# EXT_SLOT.net
KiCad netlist of a schematic drawn in Altium Designer
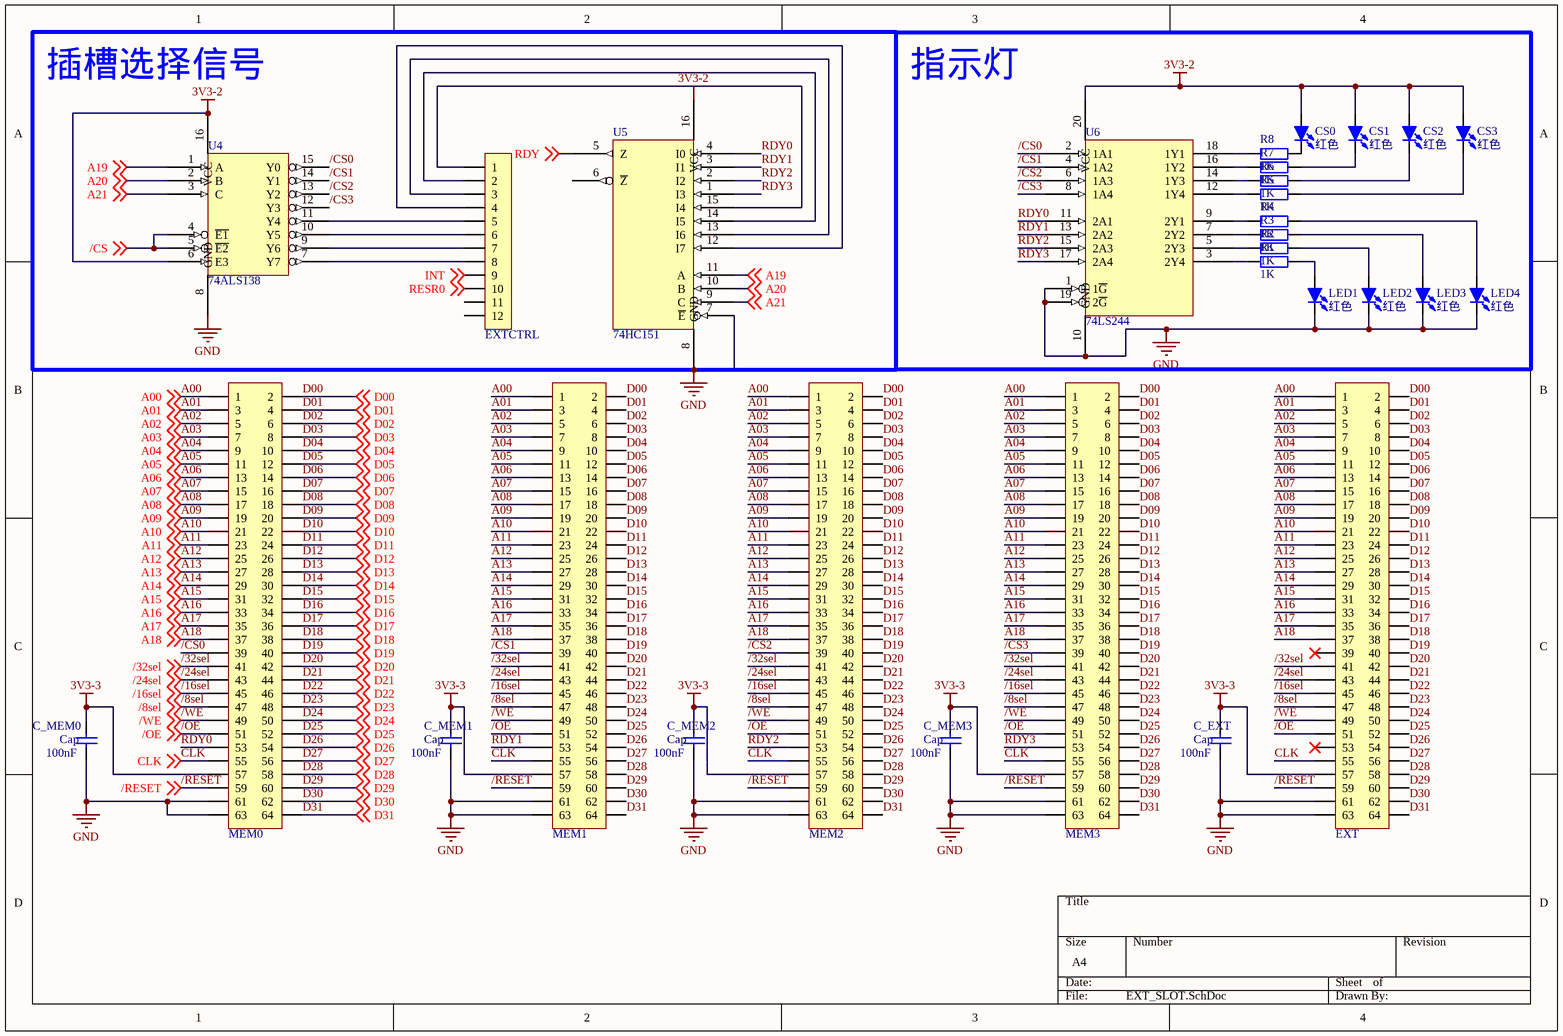
[diagram p0: EXT_SLOT.SchDoc]

(export (version "E")
  (design (tool "Eeschema 10.0.6"))
  (components
    (comp (ref "CS0")
      (value "红色")
      (footprint "LED 5MM-B")
      (description "5mm插件LED")
      (libsource (lib "9.1   - LED") (part "LED-5MM"))
    )
    (comp (ref "CS1")
      (value "红色")
      (footprint "LED 5MM-B")
      (description "5mm插件LED")
      (libsource (lib "9.1   - LED") (part "LED-5MM"))
    )
    (comp (ref "CS2")
      (value "红色")
      (footprint "LED 5MM-B")
      (description "5mm插件LED")
      (libsource (lib "9.1   - LED") (part "LED-5MM"))
    )
    (comp (ref "CS3")
      (value "红色")
      (footprint "LED 5MM-B")
      (description "5mm插件LED")
      (libsource (lib "9.1   - LED") (part "LED-5MM"))
    )
    (comp (ref "C_EXT")
      (value "Cap")
      (footprint "0805")
      (description "Capacitor")
      (fields (field (name "ALTIUM_VALUE") "100nF") (field (name "PUBLISHER") "Altium Limited"))
      (libsource (lib "Miscellaneous Devices") (part "Cap"))
    )
    (comp (ref "C_MEM0")
      (value "Cap")
      (footprint "0805")
      (description "Capacitor")
      (fields (field (name "ALTIUM_VALUE") "100nF") (field (name "PUBLISHER") "Altium Limited"))
      (libsource (lib "Miscellaneous Devices") (part "Cap"))
    )
    (comp (ref "C_MEM1")
      (value "Cap")
      (footprint "0805")
      (description "Capacitor")
      (fields (field (name "ALTIUM_VALUE") "100nF") (field (name "PUBLISHER") "Altium Limited"))
      (libsource (lib "Miscellaneous Devices") (part "Cap"))
    )
    (comp (ref "C_MEM2")
      (value "Cap")
      (footprint "0805")
      (description "Capacitor")
      (fields (field (name "ALTIUM_VALUE") "100nF") (field (name "PUBLISHER") "Altium Limited"))
      (libsource (lib "Miscellaneous Devices") (part "Cap"))
    )
    (comp (ref "C_MEM3")
      (value "Cap")
      (footprint "0805")
      (description "Capacitor")
      (fields (field (name "ALTIUM_VALUE") "100nF") (field (name "PUBLISHER") "Altium Limited"))
      (libsource (lib "Miscellaneous Devices") (part "Cap"))
    )
    (comp (ref "EXT")
      (value "Header 2X32")
      (footprint "IDC2.54-V64D")
      (description "32*2P接插件")
      (libsource (lib "4.5   - 接插件-脚距2.54") (part "Header 32X2"))
    )
    (comp (ref "EXTCTRL")
      (value "HDR-1X12")
      (footprint "SIP12")
      (description "12P接插件")
      (libsource (lib "4.5   - 接插件-脚距2.54") (part "Header 12"))
    )
    (comp (ref "LED1")
      (value "红色")
      (footprint "LED 5MM-B")
      (description "5mm插件LED")
      (libsource (lib "9.1   - LED") (part "LED-5MM"))
    )
    (comp (ref "LED2")
      (value "红色")
      (footprint "LED 5MM-B")
      (description "5mm插件LED")
      (libsource (lib "9.1   - LED") (part "LED-5MM"))
    )
    (comp (ref "LED3")
      (value "红色")
      (footprint "LED 5MM-B")
      (description "5mm插件LED")
      (libsource (lib "9.1   - LED") (part "LED-5MM"))
    )
    (comp (ref "LED4")
      (value "红色")
      (footprint "LED 5MM-B")
      (description "5mm插件LED")
      (libsource (lib "9.1   - LED") (part "LED-5MM"))
    )
    (comp (ref "MEM0")
      (value "Header 2X32")
      (footprint "IDC2.54-V64D")
      (description "32*2P接插件")
      (libsource (lib "4.5   - 接插件-脚距2.54") (part "Header 32X2"))
    )
    (comp (ref "MEM1")
      (value "Header 2X32")
      (footprint "IDC2.54-V64D")
      (description "32*2P接插件")
      (libsource (lib "4.5   - 接插件-脚距2.54") (part "Header 32X2"))
    )
    (comp (ref "MEM2")
      (value "Header 2X32")
      (footprint "IDC2.54-V64D")
      (description "32*2P接插件")
      (libsource (lib "4.5   - 接插件-脚距2.54") (part "Header 32X2"))
    )
    (comp (ref "MEM3")
      (value "Header 2X32")
      (footprint "IDC2.54-V64D")
      (description "32*2P接插件")
      (libsource (lib "4.5   - 接插件-脚距2.54") (part "Header 32X2"))
    )
    (comp (ref "R1")
      (value "1K")
      (footprint "0805")
      (description "贴片电阻")
      (libsource (lib "3.1   - 电阻-电容-电感") (part "R"))
    )
    (comp (ref "R2")
      (value "1K")
      (footprint "0805")
      (description "贴片电阻")
      (libsource (lib "3.1   - 电阻-电容-电感") (part "R"))
    )
    (comp (ref "R3")
      (value "1K")
      (footprint "0805")
      (description "贴片电阻")
      (libsource (lib "3.1   - 电阻-电容-电感") (part "R"))
    )
    (comp (ref "R4")
      (value "1K")
      (footprint "0805")
      (description "贴片电阻")
      (libsource (lib "3.1   - 电阻-电容-电感") (part "R"))
    )
    (comp (ref "R5")
      (value "1K")
      (footprint "0805")
      (description "贴片电阻")
      (libsource (lib "3.1   - 电阻-电容-电感") (part "R"))
    )
    (comp (ref "R6")
      (value "1K")
      (footprint "0805")
      (description "贴片电阻")
      (libsource (lib "3.1   - 电阻-电容-电感") (part "R"))
    )
    (comp (ref "R7")
      (value "1K")
      (footprint "0805")
      (description "贴片电阻")
      (libsource (lib "3.1   - 电阻-电容-电感") (part "R"))
    )
    (comp (ref "R8")
      (value "1K")
      (footprint "0805")
      (description "贴片电阻")
      (libsource (lib "3.1   - 电阻-电容-电感") (part "R"))
    )
    (comp (ref "U4") (value "74ALS138") (footprint "SO-16") (libsource (lib "TTL74系列IC") (part "74ALS138")))
    (comp (ref "U5") (value "74HC151") (footprint "SO-16") (libsource (lib "TTL74系列IC") (part "74HC151")))
    (comp (ref "U6") (value "74LS244") (footprint "SOJ-20") (libsource (lib "TTL74系列IC") (part "74LS244")))
  )
  (nets
    (net (code "2") (name "/RDY0") (class "Default")
      (node (ref "MEM0") (pin "53") (pinfunction "53_53") (pintype "passive"))
      (node (ref "U5") (pin "4") (pinfunction "I0_4") (pintype "input"))
      (node (ref "U6") (pin "11") (pinfunction "2A1_11") (pintype "input"))
    )
    (net (code "3") (name "/RDY1") (class "Default")
      (node (ref "MEM1") (pin "53") (pinfunction "53_53") (pintype "passive"))
      (node (ref "U5") (pin "3") (pinfunction "I1_3") (pintype "input"))
      (node (ref "U6") (pin "13") (pinfunction "2A2_13") (pintype "input"))
    )
    (net (code "4") (name "/RDY2") (class "Default")
      (node (ref "MEM2") (pin "53") (pinfunction "53_53") (pintype "passive"))
      (node (ref "U5") (pin "2") (pinfunction "I2_2") (pintype "input"))
      (node (ref "U6") (pin "15") (pinfunction "2A3_15") (pintype "input"))
    )
    (net (code "5") (name "/RDY3") (class "Default")
      (node (ref "MEM3") (pin "53") (pinfunction "53_53") (pintype "passive"))
      (node (ref "U5") (pin "1") (pinfunction "I3_1") (pintype "input"))
      (node (ref "U6") (pin "17") (pinfunction "2A4_17") (pintype "input"))
    )
    (net (code "6") (name "/{slash}CS0") (class "Default")
      (node (ref "MEM0") (pin "39") (pinfunction "39_39") (pintype "passive"))
      (node (ref "U4") (pin "15") (pinfunction "Y0_15") (pintype "output"))
      (node (ref "U6") (pin "2") (pinfunction "1A1_2") (pintype "input"))
    )
    (net (code "7") (name "/{slash}CS1") (class "Default")
      (node (ref "MEM1") (pin "39") (pinfunction "39_39") (pintype "passive"))
      (node (ref "U4") (pin "14") (pinfunction "Y1_14") (pintype "output"))
      (node (ref "U6") (pin "4") (pinfunction "1A2_4") (pintype "input"))
    )
    (net (code "8") (name "/{slash}CS2") (class "Default")
      (node (ref "MEM2") (pin "39") (pinfunction "39_39") (pintype "passive"))
      (node (ref "U4") (pin "13") (pinfunction "Y2_13") (pintype "output"))
      (node (ref "U6") (pin "6") (pinfunction "1A3_6") (pintype "input"))
    )
    (net (code "9") (name "/{slash}CS3") (class "Default")
      (node (ref "MEM3") (pin "39") (pinfunction "39_39") (pintype "passive"))
      (node (ref "U4") (pin "12") (pinfunction "Y3_12") (pintype "output"))
      (node (ref "U6") (pin "8") (pinfunction "1A4_8") (pintype "input"))
    )
    (net (code "10") (name "3V3-2") (class "Default")
      (node (ref "CS0") (pin "1") (pinfunction "A_1") (pintype "passive"))
      (node (ref "CS1") (pin "1") (pinfunction "A_1") (pintype "passive"))
      (node (ref "CS2") (pin "1") (pinfunction "A_1") (pintype "passive"))
      (node (ref "CS3") (pin "1") (pinfunction "A_1") (pintype "passive"))
      (node (ref "U4") (pin "16") (pinfunction "VCC_16") (pintype "power_in"))
      (node (ref "U4") (pin "6") (pinfunction "E3_6") (pintype "input"))
      (node (ref "U5") (pin "16") (pinfunction "VCC_16") (pintype "power_in"))
      (node (ref "U6") (pin "20") (pinfunction "VCC_20") (pintype "power_in"))
    )
    (net (code "11") (name "3V3-3") (class "Default")
      (node (ref "C_EXT") (pin "2") (pinfunction "2_2") (pintype "passive"))
      (node (ref "C_MEM0") (pin "2") (pinfunction "2_2") (pintype "passive"))
      (node (ref "C_MEM1") (pin "2") (pinfunction "2_2") (pintype "passive"))
      (node (ref "C_MEM2") (pin "2") (pinfunction "2_2") (pintype "passive"))
      (node (ref "C_MEM3") (pin "2") (pinfunction "2_2") (pintype "passive"))
      (node (ref "EXT") (pin "57") (pinfunction "57_57") (pintype "passive"))
      (node (ref "MEM0") (pin "57") (pinfunction "57_57") (pintype "passive"))
      (node (ref "MEM1") (pin "57") (pinfunction "57_57") (pintype "passive"))
      (node (ref "MEM2") (pin "57") (pinfunction "57_57") (pintype "passive"))
      (node (ref "MEM3") (pin "57") (pinfunction "57_57") (pintype "passive"))
    )
    (net (code "12") (name "A00") (class "Default")
      (node (ref "EXT") (pin "1") (pinfunction "1_1") (pintype "passive"))
      (node (ref "MEM0") (pin "1") (pinfunction "1_1") (pintype "passive"))
      (node (ref "MEM1") (pin "1") (pinfunction "1_1") (pintype "passive"))
      (node (ref "MEM2") (pin "1") (pinfunction "1_1") (pintype "passive"))
      (node (ref "MEM3") (pin "1") (pinfunction "1_1") (pintype "passive"))
    )
    (net (code "13") (name "A01") (class "Default")
      (node (ref "EXT") (pin "3") (pinfunction "3_3") (pintype "passive"))
      (node (ref "MEM0") (pin "3") (pinfunction "3_3") (pintype "passive"))
      (node (ref "MEM1") (pin "3") (pinfunction "3_3") (pintype "passive"))
      (node (ref "MEM2") (pin "3") (pinfunction "3_3") (pintype "passive"))
      (node (ref "MEM3") (pin "3") (pinfunction "3_3") (pintype "passive"))
    )
    (net (code "14") (name "A02") (class "Default")
      (node (ref "EXT") (pin "5") (pinfunction "5_5") (pintype "passive"))
      (node (ref "MEM0") (pin "5") (pinfunction "5_5") (pintype "passive"))
      (node (ref "MEM1") (pin "5") (pinfunction "5_5") (pintype "passive"))
      (node (ref "MEM2") (pin "5") (pinfunction "5_5") (pintype "passive"))
      (node (ref "MEM3") (pin "5") (pinfunction "5_5") (pintype "passive"))
    )
    (net (code "15") (name "A03") (class "Default")
      (node (ref "EXT") (pin "7") (pinfunction "7_7") (pintype "passive"))
      (node (ref "MEM0") (pin "7") (pinfunction "7_7") (pintype "passive"))
      (node (ref "MEM1") (pin "7") (pinfunction "7_7") (pintype "passive"))
      (node (ref "MEM2") (pin "7") (pinfunction "7_7") (pintype "passive"))
      (node (ref "MEM3") (pin "7") (pinfunction "7_7") (pintype "passive"))
    )
    (net (code "16") (name "A04") (class "Default")
      (node (ref "EXT") (pin "9") (pinfunction "9_9") (pintype "passive"))
      (node (ref "MEM0") (pin "9") (pinfunction "9_9") (pintype "passive"))
      (node (ref "MEM1") (pin "9") (pinfunction "9_9") (pintype "passive"))
      (node (ref "MEM2") (pin "9") (pinfunction "9_9") (pintype "passive"))
      (node (ref "MEM3") (pin "9") (pinfunction "9_9") (pintype "passive"))
    )
    (net (code "17") (name "A05") (class "Default")
      (node (ref "EXT") (pin "11") (pinfunction "11_11") (pintype "passive"))
      (node (ref "MEM0") (pin "11") (pinfunction "11_11") (pintype "passive"))
      (node (ref "MEM1") (pin "11") (pinfunction "11_11") (pintype "passive"))
      (node (ref "MEM2") (pin "11") (pinfunction "11_11") (pintype "passive"))
      (node (ref "MEM3") (pin "11") (pinfunction "11_11") (pintype "passive"))
    )
    (net (code "18") (name "A06") (class "Default")
      (node (ref "EXT") (pin "13") (pinfunction "13_13") (pintype "passive"))
      (node (ref "MEM0") (pin "13") (pinfunction "13_13") (pintype "passive"))
      (node (ref "MEM1") (pin "13") (pinfunction "13_13") (pintype "passive"))
      (node (ref "MEM2") (pin "13") (pinfunction "13_13") (pintype "passive"))
      (node (ref "MEM3") (pin "13") (pinfunction "13_13") (pintype "passive"))
    )
    (net (code "19") (name "A07") (class "Default")
      (node (ref "EXT") (pin "15") (pinfunction "15_15") (pintype "passive"))
      (node (ref "MEM0") (pin "15") (pinfunction "15_15") (pintype "passive"))
      (node (ref "MEM1") (pin "15") (pinfunction "15_15") (pintype "passive"))
      (node (ref "MEM2") (pin "15") (pinfunction "15_15") (pintype "passive"))
      (node (ref "MEM3") (pin "15") (pinfunction "15_15") (pintype "passive"))
    )
    (net (code "20") (name "A08") (class "Default")
      (node (ref "EXT") (pin "17") (pinfunction "17_17") (pintype "passive"))
      (node (ref "MEM0") (pin "17") (pinfunction "17_17") (pintype "passive"))
      (node (ref "MEM1") (pin "17") (pinfunction "17_17") (pintype "passive"))
      (node (ref "MEM2") (pin "17") (pinfunction "17_17") (pintype "passive"))
      (node (ref "MEM3") (pin "17") (pinfunction "17_17") (pintype "passive"))
    )
    (net (code "21") (name "A09") (class "Default")
      (node (ref "EXT") (pin "19") (pinfunction "19_19") (pintype "passive"))
      (node (ref "MEM0") (pin "19") (pinfunction "19_19") (pintype "passive"))
      (node (ref "MEM1") (pin "19") (pinfunction "19_19") (pintype "passive"))
      (node (ref "MEM2") (pin "19") (pinfunction "19_19") (pintype "passive"))
      (node (ref "MEM3") (pin "19") (pinfunction "19_19") (pintype "passive"))
    )
    (net (code "22") (name "A10") (class "Default")
      (node (ref "EXT") (pin "21") (pinfunction "21_21") (pintype "passive"))
      (node (ref "MEM0") (pin "21") (pinfunction "21_21") (pintype "passive"))
      (node (ref "MEM1") (pin "21") (pinfunction "21_21") (pintype "passive"))
      (node (ref "MEM2") (pin "21") (pinfunction "21_21") (pintype "passive"))
      (node (ref "MEM3") (pin "21") (pinfunction "21_21") (pintype "passive"))
    )
    (net (code "23") (name "A11") (class "Default")
      (node (ref "EXT") (pin "23") (pinfunction "23_23") (pintype "passive"))
      (node (ref "MEM0") (pin "23") (pinfunction "23_23") (pintype "passive"))
      (node (ref "MEM1") (pin "23") (pinfunction "23_23") (pintype "passive"))
      (node (ref "MEM2") (pin "23") (pinfunction "23_23") (pintype "passive"))
      (node (ref "MEM3") (pin "23") (pinfunction "23_23") (pintype "passive"))
    )
    (net (code "24") (name "A12") (class "Default")
      (node (ref "EXT") (pin "25") (pinfunction "25_25") (pintype "passive"))
      (node (ref "MEM0") (pin "25") (pinfunction "25_25") (pintype "passive"))
      (node (ref "MEM1") (pin "25") (pinfunction "25_25") (pintype "passive"))
      (node (ref "MEM2") (pin "25") (pinfunction "25_25") (pintype "passive"))
      (node (ref "MEM3") (pin "25") (pinfunction "25_25") (pintype "passive"))
    )
    (net (code "25") (name "A13") (class "Default")
      (node (ref "EXT") (pin "27") (pinfunction "27_27") (pintype "passive"))
      (node (ref "MEM0") (pin "27") (pinfunction "27_27") (pintype "passive"))
      (node (ref "MEM1") (pin "27") (pinfunction "27_27") (pintype "passive"))
      (node (ref "MEM2") (pin "27") (pinfunction "27_27") (pintype "passive"))
      (node (ref "MEM3") (pin "27") (pinfunction "27_27") (pintype "passive"))
    )
    (net (code "26") (name "A14") (class "Default")
      (node (ref "EXT") (pin "29") (pinfunction "29_29") (pintype "passive"))
      (node (ref "MEM0") (pin "29") (pinfunction "29_29") (pintype "passive"))
      (node (ref "MEM1") (pin "29") (pinfunction "29_29") (pintype "passive"))
      (node (ref "MEM2") (pin "29") (pinfunction "29_29") (pintype "passive"))
      (node (ref "MEM3") (pin "29") (pinfunction "29_29") (pintype "passive"))
    )
    (net (code "27") (name "A15") (class "Default")
      (node (ref "EXT") (pin "31") (pinfunction "31_31") (pintype "passive"))
      (node (ref "MEM0") (pin "31") (pinfunction "31_31") (pintype "passive"))
      (node (ref "MEM1") (pin "31") (pinfunction "31_31") (pintype "passive"))
      (node (ref "MEM2") (pin "31") (pinfunction "31_31") (pintype "passive"))
      (node (ref "MEM3") (pin "31") (pinfunction "31_31") (pintype "passive"))
    )
    (net (code "28") (name "A16") (class "Default")
      (node (ref "EXT") (pin "33") (pinfunction "33_33") (pintype "passive"))
      (node (ref "MEM0") (pin "33") (pinfunction "33_33") (pintype "passive"))
      (node (ref "MEM1") (pin "33") (pinfunction "33_33") (pintype "passive"))
      (node (ref "MEM2") (pin "33") (pinfunction "33_33") (pintype "passive"))
      (node (ref "MEM3") (pin "33") (pinfunction "33_33") (pintype "passive"))
    )
    (net (code "29") (name "A17") (class "Default")
      (node (ref "EXT") (pin "35") (pinfunction "35_35") (pintype "passive"))
      (node (ref "MEM0") (pin "35") (pinfunction "35_35") (pintype "passive"))
      (node (ref "MEM1") (pin "35") (pinfunction "35_35") (pintype "passive"))
      (node (ref "MEM2") (pin "35") (pinfunction "35_35") (pintype "passive"))
      (node (ref "MEM3") (pin "35") (pinfunction "35_35") (pintype "passive"))
    )
    (net (code "30") (name "A18") (class "Default")
      (node (ref "EXT") (pin "37") (pinfunction "37_37") (pintype "passive"))
      (node (ref "MEM0") (pin "37") (pinfunction "37_37") (pintype "passive"))
      (node (ref "MEM1") (pin "37") (pinfunction "37_37") (pintype "passive"))
      (node (ref "MEM2") (pin "37") (pinfunction "37_37") (pintype "passive"))
      (node (ref "MEM3") (pin "37") (pinfunction "37_37") (pintype "passive"))
    )
    (net (code "31") (name "A19") (class "Default")
      (node (ref "U4") (pin "1") (pinfunction "A_1") (pintype "input"))
      (node (ref "U5") (pin "11") (pinfunction "A_11") (pintype "input"))
    )
    (net (code "32") (name "A20") (class "Default")
      (node (ref "U4") (pin "2") (pinfunction "B_2") (pintype "input"))
      (node (ref "U5") (pin "10") (pinfunction "B_10") (pintype "input"))
    )
    (net (code "33") (name "A21") (class "Default")
      (node (ref "U4") (pin "3") (pinfunction "C_3") (pintype "input"))
      (node (ref "U5") (pin "9") (pinfunction "C_9") (pintype "input"))
    )
    (net (code "34") (name "CLK") (class "Default")
      (node (ref "EXT") (pin "55") (pinfunction "55_55") (pintype "passive"))
      (node (ref "MEM0") (pin "55") (pinfunction "55_55") (pintype "passive"))
      (node (ref "MEM1") (pin "55") (pinfunction "55_55") (pintype "passive"))
      (node (ref "MEM2") (pin "55") (pinfunction "55_55") (pintype "passive"))
      (node (ref "MEM3") (pin "55") (pinfunction "55_55") (pintype "passive"))
    )
    (net (code "35") (name "D00") (class "Default")
      (node (ref "EXT") (pin "2") (pinfunction "2_2") (pintype "passive"))
      (node (ref "MEM0") (pin "2") (pinfunction "2_2") (pintype "passive"))
      (node (ref "MEM1") (pin "2") (pinfunction "2_2") (pintype "passive"))
      (node (ref "MEM2") (pin "2") (pinfunction "2_2") (pintype "passive"))
      (node (ref "MEM3") (pin "2") (pinfunction "2_2") (pintype "passive"))
    )
    (net (code "36") (name "D01") (class "Default")
      (node (ref "EXT") (pin "4") (pinfunction "4_4") (pintype "passive"))
      (node (ref "MEM0") (pin "4") (pinfunction "4_4") (pintype "passive"))
      (node (ref "MEM1") (pin "4") (pinfunction "4_4") (pintype "passive"))
      (node (ref "MEM2") (pin "4") (pinfunction "4_4") (pintype "passive"))
      (node (ref "MEM3") (pin "4") (pinfunction "4_4") (pintype "passive"))
    )
    (net (code "37") (name "D02") (class "Default")
      (node (ref "EXT") (pin "6") (pinfunction "6_6") (pintype "passive"))
      (node (ref "MEM0") (pin "6") (pinfunction "6_6") (pintype "passive"))
      (node (ref "MEM1") (pin "6") (pinfunction "6_6") (pintype "passive"))
      (node (ref "MEM2") (pin "6") (pinfunction "6_6") (pintype "passive"))
      (node (ref "MEM3") (pin "6") (pinfunction "6_6") (pintype "passive"))
    )
    (net (code "38") (name "D03") (class "Default")
      (node (ref "EXT") (pin "8") (pinfunction "8_8") (pintype "passive"))
      (node (ref "MEM0") (pin "8") (pinfunction "8_8") (pintype "passive"))
      (node (ref "MEM1") (pin "8") (pinfunction "8_8") (pintype "passive"))
      (node (ref "MEM2") (pin "8") (pinfunction "8_8") (pintype "passive"))
      (node (ref "MEM3") (pin "8") (pinfunction "8_8") (pintype "passive"))
    )
    (net (code "39") (name "D04") (class "Default")
      (node (ref "EXT") (pin "10") (pinfunction "10_10") (pintype "passive"))
      (node (ref "MEM0") (pin "10") (pinfunction "10_10") (pintype "passive"))
      (node (ref "MEM1") (pin "10") (pinfunction "10_10") (pintype "passive"))
      (node (ref "MEM2") (pin "10") (pinfunction "10_10") (pintype "passive"))
      (node (ref "MEM3") (pin "10") (pinfunction "10_10") (pintype "passive"))
    )
    (net (code "40") (name "D05") (class "Default")
      (node (ref "EXT") (pin "12") (pinfunction "12_12") (pintype "passive"))
      (node (ref "MEM0") (pin "12") (pinfunction "12_12") (pintype "passive"))
      (node (ref "MEM1") (pin "12") (pinfunction "12_12") (pintype "passive"))
      (node (ref "MEM2") (pin "12") (pinfunction "12_12") (pintype "passive"))
      (node (ref "MEM3") (pin "12") (pinfunction "12_12") (pintype "passive"))
    )
    (net (code "41") (name "D06") (class "Default")
      (node (ref "EXT") (pin "14") (pinfunction "14_14") (pintype "passive"))
      (node (ref "MEM0") (pin "14") (pinfunction "14_14") (pintype "passive"))
      (node (ref "MEM1") (pin "14") (pinfunction "14_14") (pintype "passive"))
      (node (ref "MEM2") (pin "14") (pinfunction "14_14") (pintype "passive"))
      (node (ref "MEM3") (pin "14") (pinfunction "14_14") (pintype "passive"))
    )
    (net (code "42") (name "D07") (class "Default")
      (node (ref "EXT") (pin "16") (pinfunction "16_16") (pintype "passive"))
      (node (ref "MEM0") (pin "16") (pinfunction "16_16") (pintype "passive"))
      (node (ref "MEM1") (pin "16") (pinfunction "16_16") (pintype "passive"))
      (node (ref "MEM2") (pin "16") (pinfunction "16_16") (pintype "passive"))
      (node (ref "MEM3") (pin "16") (pinfunction "16_16") (pintype "passive"))
    )
    (net (code "43") (name "D08") (class "Default")
      (node (ref "EXT") (pin "18") (pinfunction "18_18") (pintype "passive"))
      (node (ref "MEM0") (pin "18") (pinfunction "18_18") (pintype "passive"))
      (node (ref "MEM1") (pin "18") (pinfunction "18_18") (pintype "passive"))
      (node (ref "MEM2") (pin "18") (pinfunction "18_18") (pintype "passive"))
      (node (ref "MEM3") (pin "18") (pinfunction "18_18") (pintype "passive"))
    )
    (net (code "44") (name "D09") (class "Default")
      (node (ref "EXT") (pin "20") (pinfunction "20_20") (pintype "passive"))
      (node (ref "MEM0") (pin "20") (pinfunction "20_20") (pintype "passive"))
      (node (ref "MEM1") (pin "20") (pinfunction "20_20") (pintype "passive"))
      (node (ref "MEM2") (pin "20") (pinfunction "20_20") (pintype "passive"))
      (node (ref "MEM3") (pin "20") (pinfunction "20_20") (pintype "passive"))
    )
    (net (code "45") (name "D10") (class "Default")
      (node (ref "EXT") (pin "22") (pinfunction "22_22") (pintype "passive"))
      (node (ref "MEM0") (pin "22") (pinfunction "22_22") (pintype "passive"))
      (node (ref "MEM1") (pin "22") (pinfunction "22_22") (pintype "passive"))
      (node (ref "MEM2") (pin "22") (pinfunction "22_22") (pintype "passive"))
      (node (ref "MEM3") (pin "22") (pinfunction "22_22") (pintype "passive"))
    )
    (net (code "46") (name "D11") (class "Default")
      (node (ref "EXT") (pin "24") (pinfunction "24_24") (pintype "passive"))
      (node (ref "MEM0") (pin "24") (pinfunction "24_24") (pintype "passive"))
      (node (ref "MEM1") (pin "24") (pinfunction "24_24") (pintype "passive"))
      (node (ref "MEM2") (pin "24") (pinfunction "24_24") (pintype "passive"))
      (node (ref "MEM3") (pin "24") (pinfunction "24_24") (pintype "passive"))
    )
    (net (code "47") (name "D12") (class "Default")
      (node (ref "EXT") (pin "26") (pinfunction "26_26") (pintype "passive"))
      (node (ref "MEM0") (pin "26") (pinfunction "26_26") (pintype "passive"))
      (node (ref "MEM1") (pin "26") (pinfunction "26_26") (pintype "passive"))
      (node (ref "MEM2") (pin "26") (pinfunction "26_26") (pintype "passive"))
      (node (ref "MEM3") (pin "26") (pinfunction "26_26") (pintype "passive"))
    )
    (net (code "48") (name "D13") (class "Default")
      (node (ref "EXT") (pin "28") (pinfunction "28_28") (pintype "passive"))
      (node (ref "MEM0") (pin "28") (pinfunction "28_28") (pintype "passive"))
      (node (ref "MEM1") (pin "28") (pinfunction "28_28") (pintype "passive"))
      (node (ref "MEM2") (pin "28") (pinfunction "28_28") (pintype "passive"))
      (node (ref "MEM3") (pin "28") (pinfunction "28_28") (pintype "passive"))
    )
    (net (code "49") (name "D14") (class "Default")
      (node (ref "EXT") (pin "30") (pinfunction "30_30") (pintype "passive"))
      (node (ref "MEM0") (pin "30") (pinfunction "30_30") (pintype "passive"))
      (node (ref "MEM1") (pin "30") (pinfunction "30_30") (pintype "passive"))
      (node (ref "MEM2") (pin "30") (pinfunction "30_30") (pintype "passive"))
      (node (ref "MEM3") (pin "30") (pinfunction "30_30") (pintype "passive"))
    )
    (net (code "50") (name "D15") (class "Default")
      (node (ref "EXT") (pin "32") (pinfunction "32_32") (pintype "passive"))
      (node (ref "MEM0") (pin "32") (pinfunction "32_32") (pintype "passive"))
      (node (ref "MEM1") (pin "32") (pinfunction "32_32") (pintype "passive"))
      (node (ref "MEM2") (pin "32") (pinfunction "32_32") (pintype "passive"))
      (node (ref "MEM3") (pin "32") (pinfunction "32_32") (pintype "passive"))
    )
    (net (code "51") (name "D16") (class "Default")
      (node (ref "EXT") (pin "34") (pinfunction "34_34") (pintype "passive"))
      (node (ref "MEM0") (pin "34") (pinfunction "34_34") (pintype "passive"))
      (node (ref "MEM1") (pin "34") (pinfunction "34_34") (pintype "passive"))
      (node (ref "MEM2") (pin "34") (pinfunction "34_34") (pintype "passive"))
      (node (ref "MEM3") (pin "34") (pinfunction "34_34") (pintype "passive"))
    )
    (net (code "52") (name "D17") (class "Default")
      (node (ref "EXT") (pin "36") (pinfunction "36_36") (pintype "passive"))
      (node (ref "MEM0") (pin "36") (pinfunction "36_36") (pintype "passive"))
      (node (ref "MEM1") (pin "36") (pinfunction "36_36") (pintype "passive"))
      (node (ref "MEM2") (pin "36") (pinfunction "36_36") (pintype "passive"))
      (node (ref "MEM3") (pin "36") (pinfunction "36_36") (pintype "passive"))
    )
    (net (code "53") (name "D18") (class "Default")
      (node (ref "EXT") (pin "38") (pinfunction "38_38") (pintype "passive"))
      (node (ref "MEM0") (pin "38") (pinfunction "38_38") (pintype "passive"))
      (node (ref "MEM1") (pin "38") (pinfunction "38_38") (pintype "passive"))
      (node (ref "MEM2") (pin "38") (pinfunction "38_38") (pintype "passive"))
      (node (ref "MEM3") (pin "38") (pinfunction "38_38") (pintype "passive"))
    )
    (net (code "54") (name "D19") (class "Default")
      (node (ref "EXT") (pin "40") (pinfunction "40_40") (pintype "passive"))
      (node (ref "MEM0") (pin "40") (pinfunction "40_40") (pintype "passive"))
      (node (ref "MEM1") (pin "40") (pinfunction "40_40") (pintype "passive"))
      (node (ref "MEM2") (pin "40") (pinfunction "40_40") (pintype "passive"))
      (node (ref "MEM3") (pin "40") (pinfunction "40_40") (pintype "passive"))
    )
    (net (code "55") (name "D20") (class "Default")
      (node (ref "EXT") (pin "42") (pinfunction "42_42") (pintype "passive"))
      (node (ref "MEM0") (pin "42") (pinfunction "42_42") (pintype "passive"))
      (node (ref "MEM1") (pin "42") (pinfunction "42_42") (pintype "passive"))
      (node (ref "MEM2") (pin "42") (pinfunction "42_42") (pintype "passive"))
      (node (ref "MEM3") (pin "42") (pinfunction "42_42") (pintype "passive"))
    )
    (net (code "56") (name "D21") (class "Default")
      (node (ref "EXT") (pin "44") (pinfunction "44_44") (pintype "passive"))
      (node (ref "MEM0") (pin "44") (pinfunction "44_44") (pintype "passive"))
      (node (ref "MEM1") (pin "44") (pinfunction "44_44") (pintype "passive"))
      (node (ref "MEM2") (pin "44") (pinfunction "44_44") (pintype "passive"))
      (node (ref "MEM3") (pin "44") (pinfunction "44_44") (pintype "passive"))
    )
    (net (code "57") (name "D22") (class "Default")
      (node (ref "EXT") (pin "46") (pinfunction "46_46") (pintype "passive"))
      (node (ref "MEM0") (pin "46") (pinfunction "46_46") (pintype "passive"))
      (node (ref "MEM1") (pin "46") (pinfunction "46_46") (pintype "passive"))
      (node (ref "MEM2") (pin "46") (pinfunction "46_46") (pintype "passive"))
      (node (ref "MEM3") (pin "46") (pinfunction "46_46") (pintype "passive"))
    )
    (net (code "58") (name "D23") (class "Default")
      (node (ref "EXT") (pin "48") (pinfunction "48_48") (pintype "passive"))
      (node (ref "MEM0") (pin "48") (pinfunction "48_48") (pintype "passive"))
      (node (ref "MEM1") (pin "48") (pinfunction "48_48") (pintype "passive"))
      (node (ref "MEM2") (pin "48") (pinfunction "48_48") (pintype "passive"))
      (node (ref "MEM3") (pin "48") (pinfunction "48_48") (pintype "passive"))
    )
    (net (code "59") (name "D24") (class "Default")
      (node (ref "EXT") (pin "50") (pinfunction "50_50") (pintype "passive"))
      (node (ref "MEM0") (pin "50") (pinfunction "50_50") (pintype "passive"))
      (node (ref "MEM1") (pin "50") (pinfunction "50_50") (pintype "passive"))
      (node (ref "MEM2") (pin "50") (pinfunction "50_50") (pintype "passive"))
      (node (ref "MEM3") (pin "50") (pinfunction "50_50") (pintype "passive"))
    )
    (net (code "60") (name "D25") (class "Default")
      (node (ref "EXT") (pin "52") (pinfunction "52_52") (pintype "passive"))
      (node (ref "MEM0") (pin "52") (pinfunction "52_52") (pintype "passive"))
      (node (ref "MEM1") (pin "52") (pinfunction "52_52") (pintype "passive"))
      (node (ref "MEM2") (pin "52") (pinfunction "52_52") (pintype "passive"))
      (node (ref "MEM3") (pin "52") (pinfunction "52_52") (pintype "passive"))
    )
    (net (code "61") (name "D26") (class "Default")
      (node (ref "EXT") (pin "54") (pinfunction "54_54") (pintype "passive"))
      (node (ref "MEM0") (pin "54") (pinfunction "54_54") (pintype "passive"))
      (node (ref "MEM1") (pin "54") (pinfunction "54_54") (pintype "passive"))
      (node (ref "MEM2") (pin "54") (pinfunction "54_54") (pintype "passive"))
      (node (ref "MEM3") (pin "54") (pinfunction "54_54") (pintype "passive"))
    )
    (net (code "62") (name "D27") (class "Default")
      (node (ref "EXT") (pin "56") (pinfunction "56_56") (pintype "passive"))
      (node (ref "MEM0") (pin "56") (pinfunction "56_56") (pintype "passive"))
      (node (ref "MEM1") (pin "56") (pinfunction "56_56") (pintype "passive"))
      (node (ref "MEM2") (pin "56") (pinfunction "56_56") (pintype "passive"))
      (node (ref "MEM3") (pin "56") (pinfunction "56_56") (pintype "passive"))
    )
    (net (code "63") (name "D28") (class "Default")
      (node (ref "EXT") (pin "58") (pinfunction "58_58") (pintype "passive"))
      (node (ref "MEM0") (pin "58") (pinfunction "58_58") (pintype "passive"))
      (node (ref "MEM1") (pin "58") (pinfunction "58_58") (pintype "passive"))
      (node (ref "MEM2") (pin "58") (pinfunction "58_58") (pintype "passive"))
      (node (ref "MEM3") (pin "58") (pinfunction "58_58") (pintype "passive"))
    )
    (net (code "64") (name "D29") (class "Default")
      (node (ref "EXT") (pin "60") (pinfunction "60_60") (pintype "passive"))
      (node (ref "MEM0") (pin "60") (pinfunction "60_60") (pintype "passive"))
      (node (ref "MEM1") (pin "60") (pinfunction "60_60") (pintype "passive"))
      (node (ref "MEM2") (pin "60") (pinfunction "60_60") (pintype "passive"))
      (node (ref "MEM3") (pin "60") (pinfunction "60_60") (pintype "passive"))
    )
    (net (code "65") (name "D30") (class "Default")
      (node (ref "EXT") (pin "62") (pinfunction "62_62") (pintype "passive"))
      (node (ref "MEM0") (pin "62") (pinfunction "62_62") (pintype "passive"))
      (node (ref "MEM1") (pin "62") (pinfunction "62_62") (pintype "passive"))
      (node (ref "MEM2") (pin "62") (pinfunction "62_62") (pintype "passive"))
      (node (ref "MEM3") (pin "62") (pinfunction "62_62") (pintype "passive"))
    )
    (net (code "66") (name "D31") (class "Default")
      (node (ref "EXT") (pin "64") (pinfunction "64_64") (pintype "passive"))
      (node (ref "MEM0") (pin "64") (pinfunction "64_64") (pintype "passive"))
      (node (ref "MEM1") (pin "64") (pinfunction "64_64") (pintype "passive"))
      (node (ref "MEM2") (pin "64") (pinfunction "64_64") (pintype "passive"))
      (node (ref "MEM3") (pin "64") (pinfunction "64_64") (pintype "passive"))
    )
    (net (code "67") (name "GND") (class "Default")
      (node (ref "C_EXT") (pin "1") (pinfunction "1_1") (pintype "passive"))
      (node (ref "C_MEM0") (pin "1") (pinfunction "1_1") (pintype "passive"))
      (node (ref "C_MEM1") (pin "1") (pinfunction "1_1") (pintype "passive"))
      (node (ref "C_MEM2") (pin "1") (pinfunction "1_1") (pintype "passive"))
      (node (ref "C_MEM3") (pin "1") (pinfunction "1_1") (pintype "passive"))
      (node (ref "EXT") (pin "61") (pinfunction "61_61") (pintype "passive"))
      (node (ref "EXT") (pin "63") (pinfunction "63_63") (pintype "passive"))
      (node (ref "LED1") (pin "2") (pinfunction "K_2") (pintype "passive"))
      (node (ref "LED2") (pin "2") (pinfunction "K_2") (pintype "passive"))
      (node (ref "LED3") (pin "2") (pinfunction "K_2") (pintype "passive"))
      (node (ref "LED4") (pin "2") (pinfunction "K_2") (pintype "passive"))
      (node (ref "MEM0") (pin "61") (pinfunction "61_61") (pintype "passive"))
      (node (ref "MEM0") (pin "63") (pinfunction "63_63") (pintype "passive"))
      (node (ref "MEM1") (pin "61") (pinfunction "61_61") (pintype "passive"))
      (node (ref "MEM1") (pin "63") (pinfunction "63_63") (pintype "passive"))
      (node (ref "MEM2") (pin "61") (pinfunction "61_61") (pintype "passive"))
      (node (ref "MEM2") (pin "63") (pinfunction "63_63") (pintype "passive"))
      (node (ref "MEM3") (pin "61") (pinfunction "61_61") (pintype "passive"))
      (node (ref "MEM3") (pin "63") (pinfunction "63_63") (pintype "passive"))
      (node (ref "U4") (pin "8") (pinfunction "GND_8") (pintype "power_in"))
      (node (ref "U5") (pin "7") (pinfunction "~{E}_7") (pintype "input"))
      (node (ref "U5") (pin "8") (pinfunction "GND_8") (pintype "power_in"))
      (node (ref "U6") (pin "1") (pinfunction "1~{G}_1") (pintype "input"))
      (node (ref "U6") (pin "10") (pinfunction "GND_10") (pintype "power_in"))
      (node (ref "U6") (pin "19") (pinfunction "2~{G}_19") (pintype "input"))
    )
    (net (code "68") (name "INT") (class "Default")
      (node (ref "EXTCTRL") (pin "9") (pinfunction "9_9") (pintype "passive"))
    )
    (net (code "69") (name "Net-(CS0-K)") (class "Default")
      (node (ref "CS0") (pin "2") (pinfunction "K_2") (pintype "passive"))
      (node (ref "R8") (pin "2") (pinfunction "2_2") (pintype "passive"))
    )
    (net (code "70") (name "Net-(CS1-K)") (class "Default")
      (node (ref "CS1") (pin "2") (pinfunction "K_2") (pintype "passive"))
      (node (ref "R7") (pin "2") (pinfunction "2_2") (pintype "passive"))
    )
    (net (code "71") (name "Net-(CS2-K)") (class "Default")
      (node (ref "CS2") (pin "2") (pinfunction "K_2") (pintype "passive"))
      (node (ref "R6") (pin "2") (pinfunction "2_2") (pintype "passive"))
    )
    (net (code "72") (name "Net-(CS3-K)") (class "Default")
      (node (ref "CS3") (pin "2") (pinfunction "K_2") (pintype "passive"))
      (node (ref "R5") (pin "2") (pinfunction "2_2") (pintype "passive"))
    )
    (net (code "73") (name "Net-(LED1-A)") (class "Default")
      (node (ref "LED1") (pin "1") (pinfunction "A_1") (pintype "passive"))
      (node (ref "R1") (pin "2") (pinfunction "2_2") (pintype "passive"))
    )
    (net (code "74") (name "Net-(LED2-A)") (class "Default")
      (node (ref "LED2") (pin "1") (pinfunction "A_1") (pintype "passive"))
      (node (ref "R2") (pin "2") (pinfunction "2_2") (pintype "passive"))
    )
    (net (code "75") (name "Net-(LED3-A)") (class "Default")
      (node (ref "LED3") (pin "1") (pinfunction "A_1") (pintype "passive"))
      (node (ref "R3") (pin "2") (pinfunction "2_2") (pintype "passive"))
    )
    (net (code "76") (name "Net-(LED4-A)") (class "Default")
      (node (ref "LED4") (pin "1") (pinfunction "A_1") (pintype "passive"))
      (node (ref "R4") (pin "2") (pinfunction "2_2") (pintype "passive"))
    )
    (net (code "77") (name "Net-(U4-Y4)") (class "Default")
      (node (ref "EXTCTRL") (pin "5") (pinfunction "5_5") (pintype "passive"))
      (node (ref "U4") (pin "11") (pinfunction "Y4_11") (pintype "output"))
    )
    (net (code "78") (name "Net-(U4-Y5)") (class "Default")
      (node (ref "EXTCTRL") (pin "6") (pinfunction "6_6") (pintype "passive"))
      (node (ref "U4") (pin "10") (pinfunction "Y5_10") (pintype "output"))
    )
    (net (code "79") (name "Net-(U4-Y6)") (class "Default")
      (node (ref "EXTCTRL") (pin "7") (pinfunction "7_7") (pintype "passive"))
      (node (ref "U4") (pin "9") (pinfunction "Y6_9") (pintype "output"))
    )
    (net (code "80") (name "Net-(U4-Y7)") (class "Default")
      (node (ref "EXTCTRL") (pin "8") (pinfunction "8_8") (pintype "passive"))
      (node (ref "U4") (pin "7") (pinfunction "Y7_7") (pintype "output"))
    )
    (net (code "81") (name "Net-(U5-I4)") (class "Default")
      (node (ref "EXTCTRL") (pin "1") (pinfunction "1_1") (pintype "passive"))
      (node (ref "U5") (pin "15") (pinfunction "I4_15") (pintype "input"))
    )
    (net (code "82") (name "Net-(U5-I5)") (class "Default")
      (node (ref "EXTCTRL") (pin "2") (pinfunction "2_2") (pintype "passive"))
      (node (ref "U5") (pin "14") (pinfunction "I5_14") (pintype "input"))
    )
    (net (code "83") (name "Net-(U5-I6)") (class "Default")
      (node (ref "EXTCTRL") (pin "3") (pinfunction "3_3") (pintype "passive"))
      (node (ref "U5") (pin "13") (pinfunction "I6_13") (pintype "input"))
    )
    (net (code "84") (name "Net-(U5-I7)") (class "Default")
      (node (ref "EXTCTRL") (pin "4") (pinfunction "4_4") (pintype "passive"))
      (node (ref "U5") (pin "12") (pinfunction "I7_12") (pintype "input"))
    )
    (net (code "85") (name "Net-(U6-1Y1)") (class "Default")
      (node (ref "R8") (pin "1") (pinfunction "1_1") (pintype "passive"))
      (node (ref "U6") (pin "18") (pinfunction "1Y1_18") (pintype "tri_state"))
    )
    (net (code "86") (name "Net-(U6-1Y2)") (class "Default")
      (node (ref "R7") (pin "1") (pinfunction "1_1") (pintype "passive"))
      (node (ref "U6") (pin "16") (pinfunction "1Y2_16") (pintype "tri_state"))
    )
    (net (code "87") (name "Net-(U6-1Y3)") (class "Default")
      (node (ref "R6") (pin "1") (pinfunction "1_1") (pintype "passive"))
      (node (ref "U6") (pin "14") (pinfunction "1Y3_14") (pintype "tri_state"))
    )
    (net (code "88") (name "Net-(U6-1Y4)") (class "Default")
      (node (ref "R5") (pin "1") (pinfunction "1_1") (pintype "passive"))
      (node (ref "U6") (pin "12") (pinfunction "1Y4_12") (pintype "tri_state"))
    )
    (net (code "89") (name "Net-(U6-2Y1)") (class "Default")
      (node (ref "R4") (pin "1") (pinfunction "1_1") (pintype "passive"))
      (node (ref "U6") (pin "9") (pinfunction "2Y1_9") (pintype "tri_state"))
    )
    (net (code "90") (name "Net-(U6-2Y2)") (class "Default")
      (node (ref "R3") (pin "1") (pinfunction "1_1") (pintype "passive"))
      (node (ref "U6") (pin "7") (pinfunction "2Y2_7") (pintype "tri_state"))
    )
    (net (code "91") (name "Net-(U6-2Y3)") (class "Default")
      (node (ref "R2") (pin "1") (pinfunction "1_1") (pintype "passive"))
      (node (ref "U6") (pin "5") (pinfunction "2Y3_5") (pintype "tri_state"))
    )
    (net (code "92") (name "Net-(U6-2Y4)") (class "Default")
      (node (ref "R1") (pin "1") (pinfunction "1_1") (pintype "passive"))
      (node (ref "U6") (pin "3") (pinfunction "2Y4_3") (pintype "tri_state"))
    )
    (net (code "93") (name "RDY") (class "Default")
      (node (ref "U5") (pin "5") (pinfunction "Z_5") (pintype "output"))
    )
    (net (code "94") (name "RESR0") (class "Default")
      (node (ref "EXTCTRL") (pin "10") (pinfunction "10_10") (pintype "passive"))
    )
    (net (code "95") (name "unconnected-(EXT-Pad39)") (class "Default")
      (node (ref "EXT") (pin "39") (pinfunction "39_39") (pintype "passive+no_connect"))
    )
    (net (code "96") (name "unconnected-(EXT-Pad53)") (class "Default")
      (node (ref "EXT") (pin "53") (pinfunction "53_53") (pintype "passive+no_connect"))
    )
    (net (code "97") (name "unconnected-(EXTCTRL-Pad11)") (class "Default")
      (node (ref "EXTCTRL") (pin "11") (pinfunction "11_11") (pintype "passive"))
    )
    (net (code "98") (name "unconnected-(EXTCTRL-Pad12)") (class "Default")
      (node (ref "EXTCTRL") (pin "12") (pinfunction "12_12") (pintype "passive"))
    )
    (net (code "99") (name "unconnected-(U5-~{Z}-Pad6)") (class "Default")
      (node (ref "U5") (pin "6") (pinfunction "~{Z}_6") (pintype "output"))
    )
    (net (code "100") (name "{slash}8sel") (class "Default")
      (node (ref "EXT") (pin "47") (pinfunction "47_47") (pintype "passive"))
      (node (ref "MEM0") (pin "47") (pinfunction "47_47") (pintype "passive"))
      (node (ref "MEM1") (pin "47") (pinfunction "47_47") (pintype "passive"))
      (node (ref "MEM2") (pin "47") (pinfunction "47_47") (pintype "passive"))
      (node (ref "MEM3") (pin "47") (pinfunction "47_47") (pintype "passive"))
    )
    (net (code "101") (name "{slash}16sel") (class "Default")
      (node (ref "EXT") (pin "45") (pinfunction "45_45") (pintype "passive"))
      (node (ref "MEM0") (pin "45") (pinfunction "45_45") (pintype "passive"))
      (node (ref "MEM1") (pin "45") (pinfunction "45_45") (pintype "passive"))
      (node (ref "MEM2") (pin "45") (pinfunction "45_45") (pintype "passive"))
      (node (ref "MEM3") (pin "45") (pinfunction "45_45") (pintype "passive"))
    )
    (net (code "102") (name "{slash}24sel") (class "Default")
      (node (ref "EXT") (pin "43") (pinfunction "43_43") (pintype "passive"))
      (node (ref "MEM0") (pin "43") (pinfunction "43_43") (pintype "passive"))
      (node (ref "MEM1") (pin "43") (pinfunction "43_43") (pintype "passive"))
      (node (ref "MEM2") (pin "43") (pinfunction "43_43") (pintype "passive"))
      (node (ref "MEM3") (pin "43") (pinfunction "43_43") (pintype "passive"))
    )
    (net (code "103") (name "{slash}32sel") (class "Default")
      (node (ref "EXT") (pin "41") (pinfunction "41_41") (pintype "passive"))
      (node (ref "MEM0") (pin "41") (pinfunction "41_41") (pintype "passive"))
      (node (ref "MEM1") (pin "41") (pinfunction "41_41") (pintype "passive"))
      (node (ref "MEM2") (pin "41") (pinfunction "41_41") (pintype "passive"))
      (node (ref "MEM3") (pin "41") (pinfunction "41_41") (pintype "passive"))
    )
    (net (code "104") (name "{slash}CS") (class "Default")
      (node (ref "U4") (pin "4") (pinfunction "~{E1}_4") (pintype "input"))
      (node (ref "U4") (pin "5") (pinfunction "~{E2}_5") (pintype "input"))
    )
    (net (code "105") (name "{slash}OE") (class "Default")
      (node (ref "EXT") (pin "51") (pinfunction "51_51") (pintype "passive"))
      (node (ref "MEM0") (pin "51") (pinfunction "51_51") (pintype "passive"))
      (node (ref "MEM1") (pin "51") (pinfunction "51_51") (pintype "passive"))
      (node (ref "MEM2") (pin "51") (pinfunction "51_51") (pintype "passive"))
      (node (ref "MEM3") (pin "51") (pinfunction "51_51") (pintype "passive"))
    )
    (net (code "106") (name "{slash}RESET") (class "Default")
      (node (ref "EXT") (pin "59") (pinfunction "59_59") (pintype "passive"))
      (node (ref "MEM0") (pin "59") (pinfunction "59_59") (pintype "passive"))
      (node (ref "MEM1") (pin "59") (pinfunction "59_59") (pintype "passive"))
      (node (ref "MEM2") (pin "59") (pinfunction "59_59") (pintype "passive"))
      (node (ref "MEM3") (pin "59") (pinfunction "59_59") (pintype "passive"))
    )
    (net (code "107") (name "{slash}WE") (class "Default")
      (node (ref "EXT") (pin "49") (pinfunction "49_49") (pintype "passive"))
      (node (ref "MEM0") (pin "49") (pinfunction "49_49") (pintype "passive"))
      (node (ref "MEM1") (pin "49") (pinfunction "49_49") (pintype "passive"))
      (node (ref "MEM2") (pin "49") (pinfunction "49_49") (pintype "passive"))
      (node (ref "MEM3") (pin "49") (pinfunction "49_49") (pintype "passive"))
    )
  )
)
